# Sheet_1_nizovie.net
KiCad netlist of a schematic drawn in Altium Designer
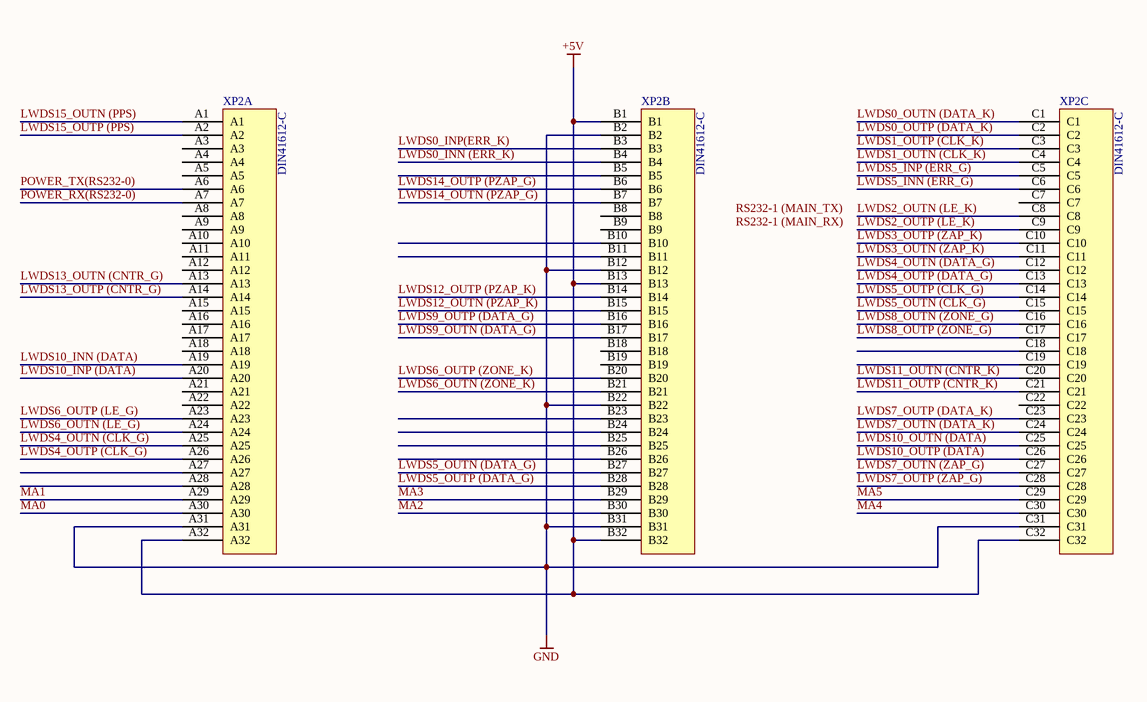
[diagram p0: Sheet_1_nizovie.SchDoc]

(export (version "E")
  (design (tool "Eeschema 10.0.6"))
  (components
    (comp (ref "XP2")
      (value "DIN41612-C")
      (footprint "DIN41612C")
      (libsource (lib "Schlib_nizovie") (part "DIN41612-C"))
    )
  )
  (nets
    (net (code "1") (name "+5V") (class "Default")
      (node (ref "XP2") (pin "A32") (pinfunction "A32_A32") (pintype "passive"))
      (node (ref "XP2") (pin "B1") (pinfunction "B1_B1") (pintype "passive"))
      (node (ref "XP2") (pin "B13") (pinfunction "B13_B13") (pintype "passive"))
      (node (ref "XP2") (pin "B32") (pinfunction "B32_B32") (pintype "passive"))
      (node (ref "XP2") (pin "C32") (pinfunction "C32_C32") (pintype "passive"))
    )
    (net (code "2") (name "/LWDS0_INN (ERR_K)") (class "Default")
      (node (ref "XP2") (pin "B4") (pinfunction "B4_B4") (pintype "passive"))
    )
    (net (code "3") (name "/LWDS0_INP(ERR_K)") (class "Default")
      (node (ref "XP2") (pin "B3") (pinfunction "B3_B3") (pintype "passive"))
    )
    (net (code "4") (name "/LWDS0_OUTN (DATA_K)") (class "Default")
      (node (ref "XP2") (pin "C1") (pinfunction "C1_C1") (pintype "passive"))
    )
    (net (code "5") (name "/LWDS0_OUTP (DATA_K)") (class "Default")
      (node (ref "XP2") (pin "C2") (pinfunction "C2_C2") (pintype "passive"))
    )
    (net (code "6") (name "/LWDS1_OUTN (CLK_K)") (class "Default")
      (node (ref "XP2") (pin "C4") (pinfunction "C4_C4") (pintype "passive"))
    )
    (net (code "7") (name "/LWDS1_OUTP (CLK_K)") (class "Default")
      (node (ref "XP2") (pin "C3") (pinfunction "C3_C3") (pintype "passive"))
    )
    (net (code "8") (name "/LWDS2_OUTN (LE_K)") (class "Default")
      (node (ref "XP2") (pin "C8") (pinfunction "C8_C8") (pintype "passive"))
    )
    (net (code "9") (name "/LWDS2_OUTP (LE_K)") (class "Default")
      (node (ref "XP2") (pin "C9") (pinfunction "C9_C9") (pintype "passive"))
    )
    (net (code "10") (name "/LWDS3_OUTN (ZAP_K)") (class "Default")
      (node (ref "XP2") (pin "C11") (pinfunction "C11_C11") (pintype "passive"))
    )
    (net (code "11") (name "/LWDS3_OUTP (ZAP_K)") (class "Default")
      (node (ref "XP2") (pin "C10") (pinfunction "C10_C10") (pintype "passive"))
    )
    (net (code "12") (name "/LWDS4_OUTN (CLK_G)") (class "Default")
      (node (ref "XP2") (pin "A25") (pinfunction "A25_A25") (pintype "passive"))
    )
    (net (code "13") (name "/LWDS4_OUTN (DATA_G)") (class "Default")
      (node (ref "XP2") (pin "C12") (pinfunction "C12_C12") (pintype "passive"))
    )
    (net (code "14") (name "/LWDS4_OUTP (CLK_G)") (class "Default")
      (node (ref "XP2") (pin "A26") (pinfunction "A26_A26") (pintype "passive"))
    )
    (net (code "15") (name "/LWDS4_OUTP (DATA_G)") (class "Default")
      (node (ref "XP2") (pin "C13") (pinfunction "C13_C13") (pintype "passive"))
    )
    (net (code "16") (name "/LWDS5_INN (ERR_G)") (class "Default")
      (node (ref "XP2") (pin "C6") (pinfunction "C6_C6") (pintype "passive"))
    )
    (net (code "17") (name "/LWDS5_INP (ERR_G)") (class "Default")
      (node (ref "XP2") (pin "C5") (pinfunction "C5_C5") (pintype "passive"))
    )
    (net (code "18") (name "/LWDS5_OUTN (CLK_G)") (class "Default")
      (node (ref "XP2") (pin "C15") (pinfunction "C15_C15") (pintype "passive"))
    )
    (net (code "19") (name "/LWDS5_OUTN (DATA_G)") (class "Default")
      (node (ref "XP2") (pin "B27") (pinfunction "B27_B27") (pintype "passive"))
    )
    (net (code "20") (name "/LWDS5_OUTP (CLK_G)") (class "Default")
      (node (ref "XP2") (pin "C14") (pinfunction "C14_C14") (pintype "passive"))
    )
    (net (code "21") (name "/LWDS5_OUTP (DATA_G)") (class "Default")
      (node (ref "XP2") (pin "B28") (pinfunction "B28_B28") (pintype "passive"))
    )
    (net (code "22") (name "/LWDS6_OUTN (LE_G)") (class "Default")
      (node (ref "XP2") (pin "A24") (pinfunction "A24_A24") (pintype "passive"))
    )
    (net (code "23") (name "/LWDS6_OUTN (ZONE_K)") (class "Default")
      (node (ref "XP2") (pin "B21") (pinfunction "B21_B21") (pintype "passive"))
    )
    (net (code "24") (name "/LWDS6_OUTP (LE_G)") (class "Default")
      (node (ref "XP2") (pin "A23") (pinfunction "A23_A23") (pintype "passive"))
    )
    (net (code "25") (name "/LWDS6_OUTP (ZONE_K)") (class "Default")
      (node (ref "XP2") (pin "B20") (pinfunction "B20_B20") (pintype "passive"))
    )
    (net (code "26") (name "/LWDS7_OUTN (DATA_K)") (class "Default")
      (node (ref "XP2") (pin "C24") (pinfunction "C24_C24") (pintype "passive"))
    )
    (net (code "27") (name "/LWDS7_OUTN (ZAP_G)") (class "Default")
      (node (ref "XP2") (pin "C27") (pinfunction "C27_C27") (pintype "passive"))
    )
    (net (code "28") (name "/LWDS7_OUTP (DATA_K)") (class "Default")
      (node (ref "XP2") (pin "C23") (pinfunction "C23_C23") (pintype "passive"))
    )
    (net (code "29") (name "/LWDS7_OUTP (ZAP_G)") (class "Default")
      (node (ref "XP2") (pin "C28") (pinfunction "C28_C28") (pintype "passive"))
    )
    (net (code "30") (name "/LWDS8_OUTN (ZONE_G)") (class "Default")
      (node (ref "XP2") (pin "C16") (pinfunction "C16_C16") (pintype "passive"))
    )
    (net (code "31") (name "/LWDS8_OUTP (ZONE_G)") (class "Default")
      (node (ref "XP2") (pin "C17") (pinfunction "C17_C17") (pintype "passive"))
    )
    (net (code "32") (name "/LWDS9_OUTN (DATA_G)") (class "Default")
      (node (ref "XP2") (pin "B17") (pinfunction "B17_B17") (pintype "passive"))
    )
    (net (code "33") (name "/LWDS9_OUTP (DATA_G)") (class "Default")
      (node (ref "XP2") (pin "B16") (pinfunction "B16_B16") (pintype "passive"))
    )
    (net (code "34") (name "/LWDS10_INN (DATA)") (class "Default")
      (node (ref "XP2") (pin "A19") (pinfunction "A19_A19") (pintype "passive"))
    )
    (net (code "35") (name "/LWDS10_INP (DATA)") (class "Default")
      (node (ref "XP2") (pin "A20") (pinfunction "A20_A20") (pintype "passive"))
    )
    (net (code "36") (name "/LWDS10_OUTN (DATA)") (class "Default")
      (node (ref "XP2") (pin "C25") (pinfunction "C25_C25") (pintype "passive"))
    )
    (net (code "37") (name "/LWDS10_OUTP (DATA)") (class "Default")
      (node (ref "XP2") (pin "C26") (pinfunction "C26_C26") (pintype "passive"))
    )
    (net (code "38") (name "/LWDS11_OUTN (CNTR_K)") (class "Default")
      (node (ref "XP2") (pin "C20") (pinfunction "C20_C20") (pintype "passive"))
    )
    (net (code "39") (name "/LWDS11_OUTP (CNTR_K)") (class "Default")
      (node (ref "XP2") (pin "C21") (pinfunction "C21_C21") (pintype "passive"))
    )
    (net (code "40") (name "/LWDS12_OUTN (PZAP_K)") (class "Default")
      (node (ref "XP2") (pin "B15") (pinfunction "B15_B15") (pintype "passive"))
    )
    (net (code "41") (name "/LWDS12_OUTP (PZAP_K)") (class "Default")
      (node (ref "XP2") (pin "B14") (pinfunction "B14_B14") (pintype "passive"))
    )
    (net (code "42") (name "/LWDS13_OUTN (CNTR_G)") (class "Default")
      (node (ref "XP2") (pin "A13") (pinfunction "A13_A13") (pintype "passive"))
    )
    (net (code "43") (name "/LWDS13_OUTP (CNTR_G)") (class "Default")
      (node (ref "XP2") (pin "A14") (pinfunction "A14_A14") (pintype "passive"))
    )
    (net (code "44") (name "/LWDS14_OUTN (PZAP_G)") (class "Default")
      (node (ref "XP2") (pin "B7") (pinfunction "B7_B7") (pintype "passive"))
    )
    (net (code "45") (name "/LWDS14_OUTP (PZAP_G)") (class "Default")
      (node (ref "XP2") (pin "B6") (pinfunction "B6_B6") (pintype "passive"))
    )
    (net (code "46") (name "/LWDS15_OUTN (PPS)") (class "Default")
      (node (ref "XP2") (pin "A1") (pinfunction "A1_A1") (pintype "passive"))
    )
    (net (code "47") (name "/LWDS15_OUTP (PPS)") (class "Default")
      (node (ref "XP2") (pin "A2") (pinfunction "A2_A2") (pintype "passive"))
    )
    (net (code "48") (name "/MA0") (class "Default")
      (node (ref "XP2") (pin "A30") (pinfunction "A30_A30") (pintype "passive"))
    )
    (net (code "49") (name "/MA1") (class "Default")
      (node (ref "XP2") (pin "A29") (pinfunction "A29_A29") (pintype "passive"))
    )
    (net (code "50") (name "/MA2") (class "Default")
      (node (ref "XP2") (pin "B30") (pinfunction "B30_B30") (pintype "passive"))
    )
    (net (code "51") (name "/MA3") (class "Default")
      (node (ref "XP2") (pin "B29") (pinfunction "B29_B29") (pintype "passive"))
    )
    (net (code "52") (name "/MA4") (class "Default")
      (node (ref "XP2") (pin "C30") (pinfunction "C30_C30") (pintype "passive"))
    )
    (net (code "53") (name "/MA5") (class "Default")
      (node (ref "XP2") (pin "C29") (pinfunction "C29_C29") (pintype "passive"))
    )
    (net (code "54") (name "/POWER_RX(RS232-0)") (class "Default")
      (node (ref "XP2") (pin "A7") (pinfunction "A7_A7") (pintype "passive"))
    )
    (net (code "55") (name "/POWER_TX(RS232-0)") (class "Default")
      (node (ref "XP2") (pin "A6") (pinfunction "A6_A6") (pintype "passive"))
    )
    (net (code "58") (name "GND") (class "Default")
      (node (ref "XP2") (pin "A31") (pinfunction "A31_A31") (pintype "passive"))
      (node (ref "XP2") (pin "B12") (pinfunction "B12_B12") (pintype "passive"))
      (node (ref "XP2") (pin "B2") (pinfunction "B2_B2") (pintype "passive"))
      (node (ref "XP2") (pin "B22") (pinfunction "B22_B22") (pintype "passive"))
      (node (ref "XP2") (pin "B31") (pinfunction "B31_B31") (pintype "passive"))
      (node (ref "XP2") (pin "C31") (pinfunction "C31_C31") (pintype "passive"))
    )
    (net (code "59") (name "unconnected-(XP2-PadA3)") (class "Default")
      (node (ref "XP2") (pin "A3") (pinfunction "A3_A3") (pintype "passive"))
    )
    (net (code "60") (name "unconnected-(XP2-PadA4)") (class "Default")
      (node (ref "XP2") (pin "A4") (pinfunction "A4_A4") (pintype "passive"))
    )
    (net (code "61") (name "unconnected-(XP2-PadA5)") (class "Default")
      (node (ref "XP2") (pin "A5") (pinfunction "A5_A5") (pintype "passive"))
    )
    (net (code "62") (name "unconnected-(XP2-PadA8)") (class "Default")
      (node (ref "XP2") (pin "A8") (pinfunction "A8_A8") (pintype "passive"))
    )
    (net (code "63") (name "unconnected-(XP2-PadA9)") (class "Default")
      (node (ref "XP2") (pin "A9") (pinfunction "A9_A9") (pintype "passive"))
    )
    (net (code "64") (name "unconnected-(XP2-PadA10)") (class "Default")
      (node (ref "XP2") (pin "A10") (pinfunction "A10_A10") (pintype "passive"))
    )
    (net (code "65") (name "unconnected-(XP2-PadA11)") (class "Default")
      (node (ref "XP2") (pin "A11") (pinfunction "A11_A11") (pintype "passive"))
    )
    (net (code "66") (name "unconnected-(XP2-PadA12)") (class "Default")
      (node (ref "XP2") (pin "A12") (pinfunction "A12_A12") (pintype "passive"))
    )
    (net (code "67") (name "unconnected-(XP2-PadA15)") (class "Default")
      (node (ref "XP2") (pin "A15") (pinfunction "A15_A15") (pintype "passive"))
    )
    (net (code "68") (name "unconnected-(XP2-PadA16)") (class "Default")
      (node (ref "XP2") (pin "A16") (pinfunction "A16_A16") (pintype "passive"))
    )
    (net (code "69") (name "unconnected-(XP2-PadA17)") (class "Default")
      (node (ref "XP2") (pin "A17") (pinfunction "A17_A17") (pintype "passive"))
    )
    (net (code "70") (name "unconnected-(XP2-PadA18)") (class "Default")
      (node (ref "XP2") (pin "A18") (pinfunction "A18_A18") (pintype "passive"))
    )
    (net (code "71") (name "unconnected-(XP2-PadA21)") (class "Default")
      (node (ref "XP2") (pin "A21") (pinfunction "A21_A21") (pintype "passive"))
    )
    (net (code "72") (name "unconnected-(XP2-PadA22)") (class "Default")
      (node (ref "XP2") (pin "A22") (pinfunction "A22_A22") (pintype "passive"))
    )
    (net (code "73") (name "unconnected-(XP2-PadA27)") (class "Default")
      (node (ref "XP2") (pin "A27") (pinfunction "A27_A27") (pintype "passive"))
    )
    (net (code "74") (name "unconnected-(XP2-PadA28)") (class "Default")
      (node (ref "XP2") (pin "A28") (pinfunction "A28_A28") (pintype "passive"))
    )
    (net (code "75") (name "unconnected-(XP2-PadB5)") (class "Default")
      (node (ref "XP2") (pin "B5") (pinfunction "B5_B5") (pintype "passive"))
    )
    (net (code "76") (name "unconnected-(XP2-PadB8)") (class "Default")
      (node (ref "XP2") (pin "B8") (pinfunction "B8_B8") (pintype "passive"))
    )
    (net (code "77") (name "unconnected-(XP2-PadB9)") (class "Default")
      (node (ref "XP2") (pin "B9") (pinfunction "B9_B9") (pintype "passive"))
    )
    (net (code "78") (name "unconnected-(XP2-PadB10)") (class "Default")
      (node (ref "XP2") (pin "B10") (pinfunction "B10_B10") (pintype "passive"))
    )
    (net (code "79") (name "unconnected-(XP2-PadB11)") (class "Default")
      (node (ref "XP2") (pin "B11") (pinfunction "B11_B11") (pintype "passive"))
    )
    (net (code "80") (name "unconnected-(XP2-PadB18)") (class "Default")
      (node (ref "XP2") (pin "B18") (pinfunction "B18_B18") (pintype "passive"))
    )
    (net (code "81") (name "unconnected-(XP2-PadB19)") (class "Default")
      (node (ref "XP2") (pin "B19") (pinfunction "B19_B19") (pintype "passive"))
    )
    (net (code "82") (name "unconnected-(XP2-PadB23)") (class "Default")
      (node (ref "XP2") (pin "B23") (pinfunction "B23_B23") (pintype "passive"))
    )
    (net (code "83") (name "unconnected-(XP2-PadB24)") (class "Default")
      (node (ref "XP2") (pin "B24") (pinfunction "B24_B24") (pintype "passive"))
    )
    (net (code "84") (name "unconnected-(XP2-PadB25)") (class "Default")
      (node (ref "XP2") (pin "B25") (pinfunction "B25_B25") (pintype "passive"))
    )
    (net (code "85") (name "unconnected-(XP2-PadB26)") (class "Default")
      (node (ref "XP2") (pin "B26") (pinfunction "B26_B26") (pintype "passive"))
    )
    (net (code "86") (name "unconnected-(XP2-PadC7)") (class "Default")
      (node (ref "XP2") (pin "C7") (pinfunction "C7_C7") (pintype "passive"))
    )
    (net (code "87") (name "unconnected-(XP2-PadC18)") (class "Default")
      (node (ref "XP2") (pin "C18") (pinfunction "C18_C18") (pintype "passive"))
    )
    (net (code "88") (name "unconnected-(XP2-PadC19)") (class "Default")
      (node (ref "XP2") (pin "C19") (pinfunction "C19_C19") (pintype "passive"))
    )
    (net (code "89") (name "unconnected-(XP2-PadC22)") (class "Default")
      (node (ref "XP2") (pin "C22") (pinfunction "C22_C22") (pintype "passive"))
    )
  )
)
